# chlorophyll_analyzer_attachment.net
KiCad netlist of a schematic drawn in EAGLE
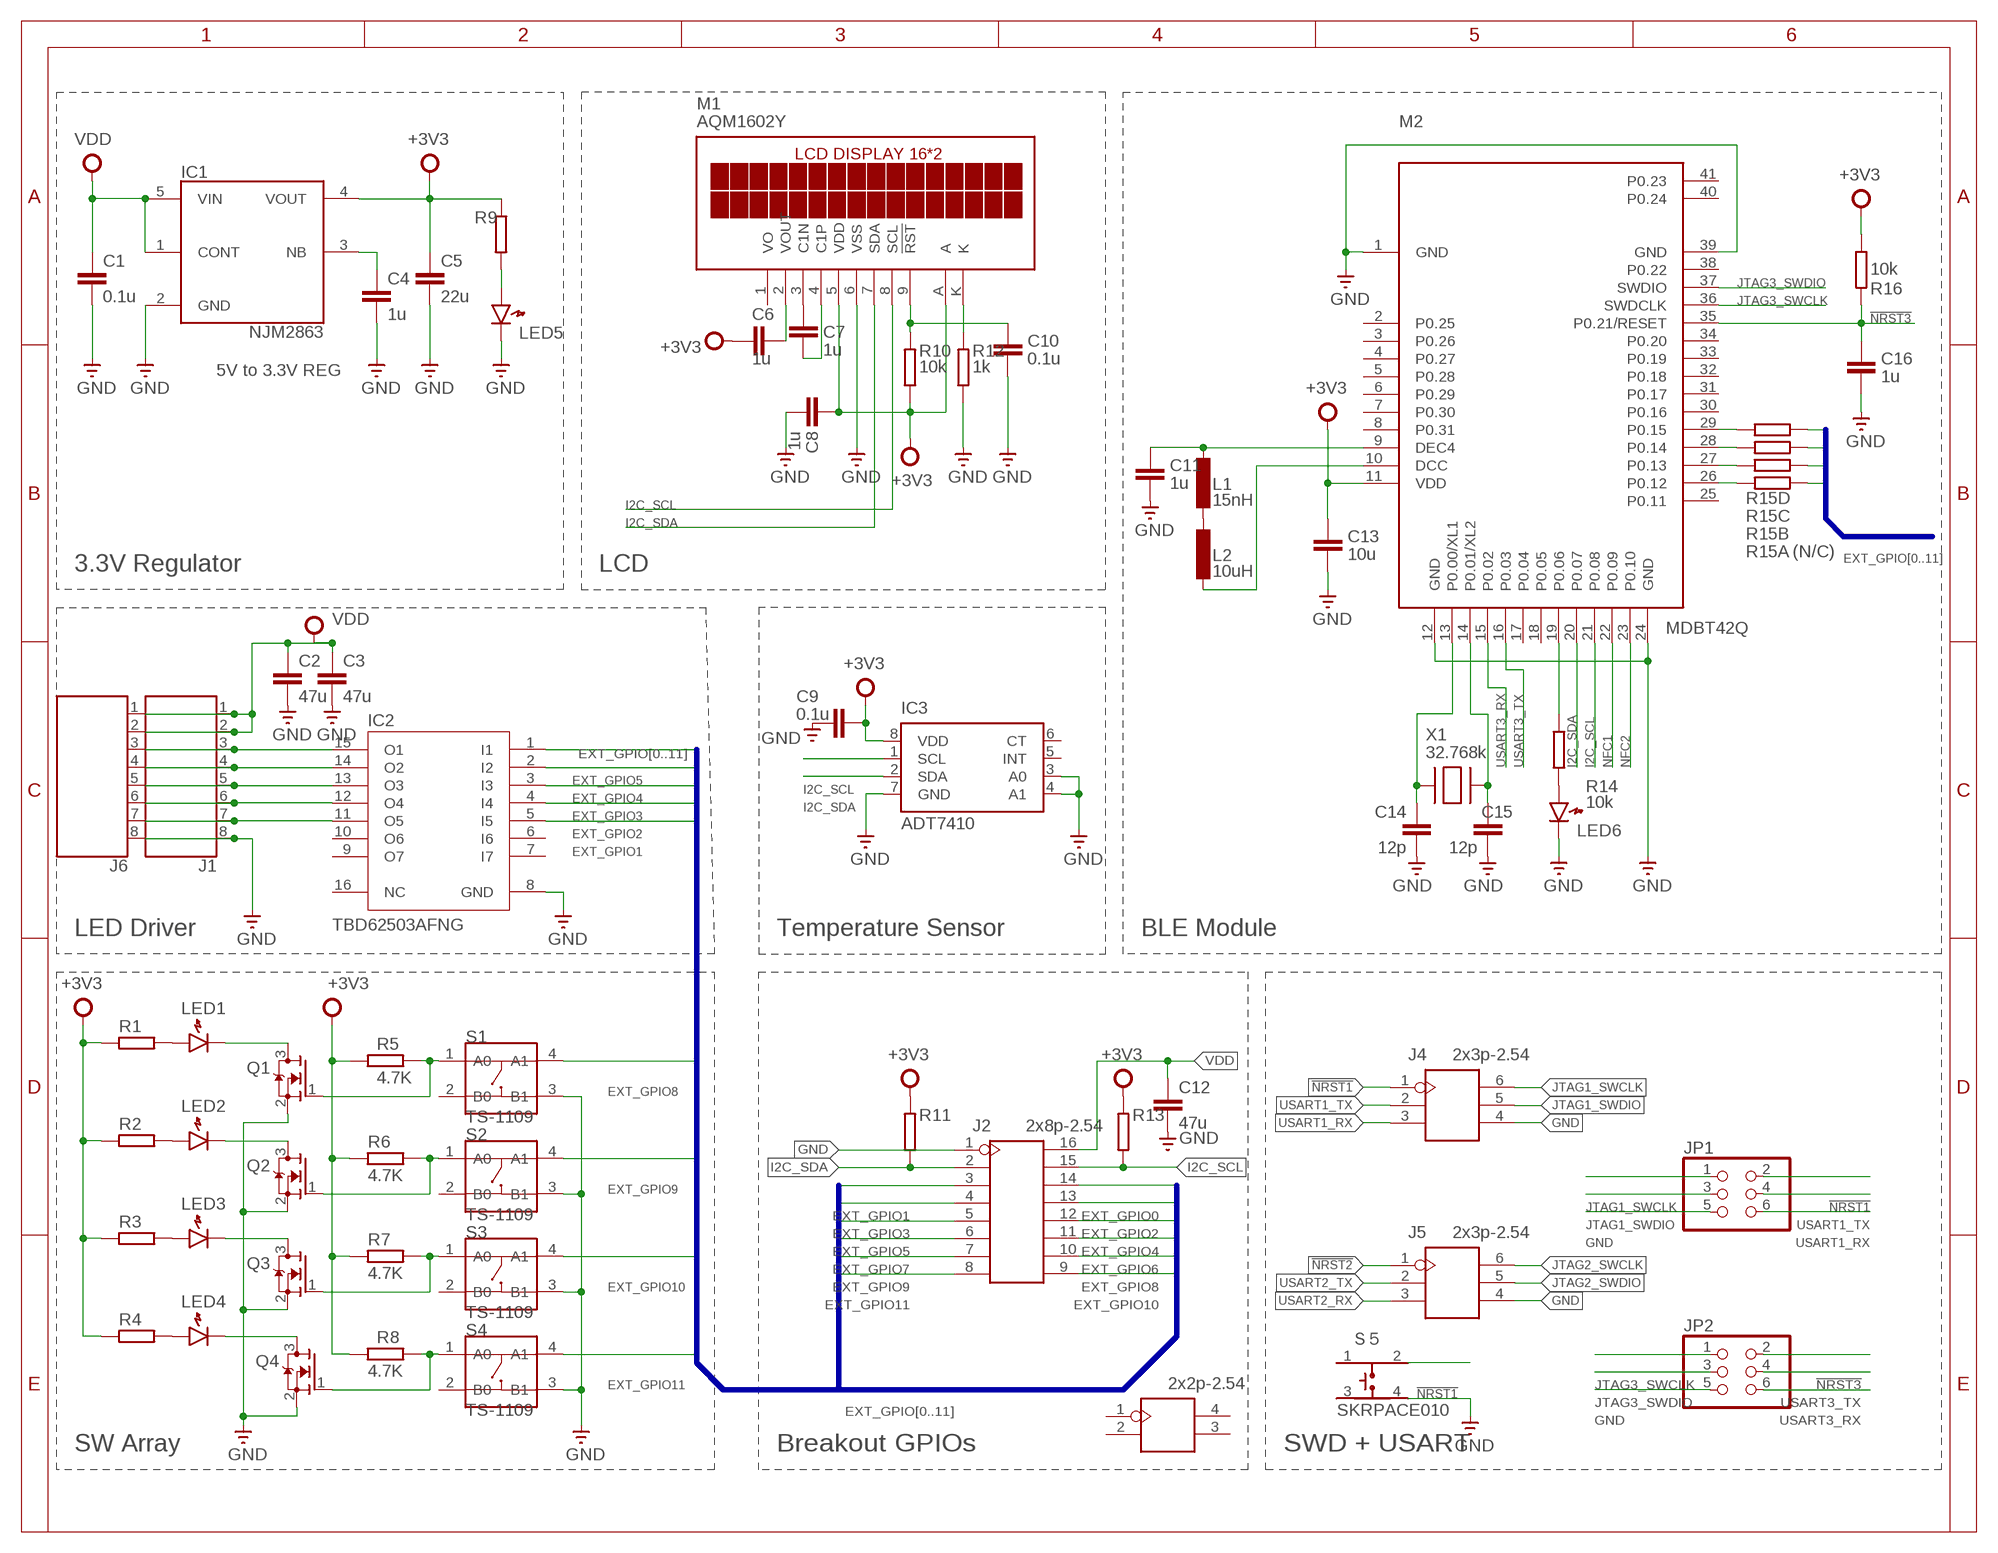
[diagram p0: schematic, sheet 1]

(export (version "E")
  (design (tool "Eeschema 10.0.6"))
  (components
    (comp (ref "C1")
      (value "0.1u")
      (footprint "eagle-import:C0603K")
      (libsource (lib "eagle-import") (part "C-EUC0603K"))
    )
    (comp (ref "C2")
      (value "47u")
      (footprint "eagle-import:C1206")
      (libsource (lib "eagle-import") (part "C-EUC1206"))
    )
    (comp (ref "C3")
      (value "47u")
      (footprint "eagle-import:C1206")
      (libsource (lib "eagle-import") (part "C-EUC1206"))
    )
    (comp (ref "C4")
      (value "1u")
      (footprint "eagle-import:C0603K")
      (libsource (lib "eagle-import") (part "C-EUC0603K"))
    )
    (comp (ref "C5")
      (value "22u")
      (footprint "eagle-import:C0603K")
      (libsource (lib "eagle-import") (part "C-EUC0603K"))
    )
    (comp (ref "C6")
      (value "1u")
      (footprint "eagle-import:C0603K")
      (libsource (lib "eagle-import") (part "C-EUC0603K"))
    )
    (comp (ref "C7")
      (value "1u")
      (footprint "eagle-import:C0603K")
      (libsource (lib "eagle-import") (part "C-EUC0603K"))
    )
    (comp (ref "C8")
      (value "1u")
      (footprint "eagle-import:C0603K")
      (libsource (lib "eagle-import") (part "C-EUC0603K"))
    )
    (comp (ref "C9")
      (value "0.1u")
      (footprint "eagle-import:C0603K")
      (libsource (lib "eagle-import") (part "C-EUC0603K"))
    )
    (comp (ref "C10")
      (value "0.1u")
      (footprint "eagle-import:C0603K")
      (libsource (lib "eagle-import") (part "C-EUC0603K"))
    )
    (comp (ref "C11")
      (value "1u")
      (footprint "eagle-import:C0603K")
      (libsource (lib "eagle-import") (part "C-EUC0603K"))
    )
    (comp (ref "C12")
      (value "47u")
      (footprint "eagle-import:C1206")
      (libsource (lib "eagle-import") (part "C-EUC1206"))
    )
    (comp (ref "C13")
      (value "10u")
      (footprint "eagle-import:C0603K")
      (libsource (lib "eagle-import") (part "C-EUC0603K"))
    )
    (comp (ref "C14")
      (value "12p")
      (footprint "eagle-import:C0603K")
      (libsource (lib "eagle-import") (part "C-EUC0603K"))
    )
    (comp (ref "C15")
      (value "12p")
      (footprint "eagle-import:C0603K")
      (libsource (lib "eagle-import") (part "C-EUC0603K"))
    )
    (comp (ref "C16")
      (value "1u")
      (footprint "eagle-import:C0603K")
      (libsource (lib "eagle-import") (part "C-EUC0603K"))
    )
    (comp (ref "IC1")
      (value "NJM2863")
      (footprint "eagle-import:SOT-23-5")
      (libsource (lib "eagle-import") (part "NJM2863"))
    )
    (comp (ref "IC2")
      (value "TBD62503AFNG")
      (footprint "eagle-import:SSOP16-P-225-0.65B")
      (libsource (lib "eagle-import") (part "TBD62503AFNG"))
    )
    (comp (ref "IC3")
      (value "ADT7410")
      (footprint "eagle-import:SOIC8")
      (fields
        (field (name "DIGI-KEY_PART_NUMBER") "ADT7410TRZ-REEL7CT-ND")
        (field (name "MF") "Analog Devices")
      )
      (libsource (lib "eagle-import") (part "ADT7410"))
    )
    (comp (ref "J1")
      (value "687108183722")
      (footprint "eagle-import:687108183722")
      (libsource (lib "eagle-import") (part "687108183722"))
    )
    (comp (ref "J2")
      (value "2x8p-2.54")
      (footprint "eagle-import:H2X8-2.54")
      (fields (field (name "MPN") "F185-1216A0BSYA1"))
      (libsource (lib "eagle-import") (part "DIP-BLACK-FEMALE-HEADER-VERT(2X8P-2.54)"))
    )
    (comp (ref "J3")
      (value "2x2p-2.54")
      (footprint "eagle-import:H2X2-2.54")
      (libsource (lib "eagle-import") (part "DIP-BLACK-FEMALE-HEADER-VERT(2X2P-2.54)"))
    )
    (comp (ref "J4")
      (value "2x3p-2.54")
      (footprint "eagle-import:H2X3-2.54")
      (fields (field (name "MPN") "F185-1203A1BSYA1"))
      (libsource (lib "eagle-import") (part "DIP-BLACK-FEMALE-HEADER-VERT(2X3P-2.54)"))
    )
    (comp (ref "J5")
      (value "2x3p-2.54")
      (footprint "eagle-import:H2X3-2.54")
      (fields (field (name "MPN") "F185-1203A1BSYA1"))
      (libsource (lib "eagle-import") (part "DIP-BLACK-FEMALE-HEADER-VERT(2X3P-2.54)"))
    )
    (comp (ref "J6")
      (value "687108183722")
      (footprint "eagle-import:687108183722")
      (libsource (lib "eagle-import") (part "687108183722"))
    )
    (comp (ref "JP1")
      (value "PINHD-2X3")
      (footprint "eagle-import:2X03")
      (libsource (lib "eagle-import") (part "PINHD-2X3"))
    )
    (comp (ref "JP2")
      (value "PINHD-2X3")
      (footprint "eagle-import:2X03")
      (libsource (lib "eagle-import") (part "PINHD-2X3"))
    )
    (comp (ref "L1")
      (value "15nH")
      (footprint "eagle-import:SMD1608")
      (libsource (lib "eagle-import") (part "INDUCOR1608"))
    )
    (comp (ref "L2")
      (value "10uH")
      (footprint "eagle-import:SMD1608")
      (libsource (lib "eagle-import") (part "INDUCOR1608"))
    )
    (comp (ref "LED1")
      (value "LED1608")
      (footprint "eagle-import:LED1608")
      (libsource (lib "eagle-import") (part "LED1608"))
    )
    (comp (ref "LED2")
      (value "LED1608")
      (footprint "eagle-import:LED1608")
      (libsource (lib "eagle-import") (part "LED1608"))
    )
    (comp (ref "LED3")
      (value "LED1608")
      (footprint "eagle-import:LED1608")
      (libsource (lib "eagle-import") (part "LED1608"))
    )
    (comp (ref "LED4")
      (value "LED1608")
      (footprint "eagle-import:LED1608")
      (libsource (lib "eagle-import") (part "LED1608"))
    )
    (comp (ref "LED5")
      (value "LED1608")
      (footprint "eagle-import:LED1608")
      (libsource (lib "eagle-import") (part "LED1608"))
    )
    (comp (ref "LED6")
      (value "LED1608")
      (footprint "eagle-import:LED1608")
      (libsource (lib "eagle-import") (part "LED1608"))
    )
    (comp (ref "M1")
      (value "AQM1602Y")
      (footprint "eagle-import:AQM1602Y")
      (libsource (lib "eagle-import") (part "AQM1602Y"))
    )
    (comp (ref "M2")
      (value "MDBT42Q")
      (footprint "eagle-import:MDBT42Q")
      (libsource (lib "eagle-import") (part "MDBT42Q"))
    )
    (comp (ref "Q1")
      (value "MOSFET-NREFLOW")
      (footprint "eagle-import:SOT23")
      (libsource (lib "eagle-import") (part "MOSFET-NREFLOW"))
    )
    (comp (ref "Q2")
      (value "MOSFET-NREFLOW")
      (footprint "eagle-import:SOT23")
      (libsource (lib "eagle-import") (part "MOSFET-NREFLOW"))
    )
    (comp (ref "Q3")
      (value "MOSFET-NREFLOW")
      (footprint "eagle-import:SOT23")
      (libsource (lib "eagle-import") (part "MOSFET-NREFLOW"))
    )
    (comp (ref "Q4")
      (value "MOSFET-NREFLOW")
      (footprint "eagle-import:SOT23")
      (libsource (lib "eagle-import") (part "MOSFET-NREFLOW"))
    )
    (comp (ref "R1")
      (value "RESISTOR1608")
      (footprint "eagle-import:SMD1608")
      (libsource (lib "eagle-import") (part "RESISTOR1608"))
    )
    (comp (ref "R2")
      (value "RESISTOR1608")
      (footprint "eagle-import:SMD1608")
      (libsource (lib "eagle-import") (part "RESISTOR1608"))
    )
    (comp (ref "R3")
      (value "RESISTOR1608")
      (footprint "eagle-import:SMD1608")
      (libsource (lib "eagle-import") (part "RESISTOR1608"))
    )
    (comp (ref "R4")
      (value "RESISTOR1608")
      (footprint "eagle-import:SMD1608")
      (libsource (lib "eagle-import") (part "RESISTOR1608"))
    )
    (comp (ref "R5")
      (value "4.7K")
      (footprint "eagle-import:SMD1608")
      (libsource (lib "eagle-import") (part "RESISTOR1608"))
    )
    (comp (ref "R6")
      (value "4.7K")
      (footprint "eagle-import:SMD1608")
      (libsource (lib "eagle-import") (part "RESISTOR1608"))
    )
    (comp (ref "R7")
      (value "4.7K")
      (footprint "eagle-import:SMD1608")
      (libsource (lib "eagle-import") (part "RESISTOR1608"))
    )
    (comp (ref "R8")
      (value "4.7K")
      (footprint "eagle-import:SMD1608")
      (libsource (lib "eagle-import") (part "RESISTOR1608"))
    )
    (comp (ref "R9")
      (value "RESISTOR1608")
      (footprint "eagle-import:SMD1608")
      (libsource (lib "eagle-import") (part "RESISTOR1608"))
    )
    (comp (ref "R10")
      (value "10k")
      (footprint "eagle-import:SMD1608")
      (libsource (lib "eagle-import") (part "RESISTOR1608"))
    )
    (comp (ref "R11")
      (value "RESISTOR1608")
      (footprint "eagle-import:SMD1608")
      (libsource (lib "eagle-import") (part "RESISTOR1608"))
    )
    (comp (ref "R12")
      (value "1k")
      (footprint "eagle-import:SMD1608")
      (libsource (lib "eagle-import") (part "RESISTOR1608"))
    )
    (comp (ref "R13")
      (value "RESISTOR1608")
      (footprint "eagle-import:SMD1608")
      (libsource (lib "eagle-import") (part "RESISTOR1608"))
    )
    (comp (ref "R14")
      (value "10k")
      (footprint "eagle-import:SMD1608")
      (libsource (lib "eagle-import") (part "RESISTOR1608"))
    )
    (comp (ref "R15")
      (value "(N/C)")
      (footprint "eagle-import:RESCAXS80P320X160X60-8N")
      (libsource (lib "eagle-import") (part "RESISTOR_ARRY1206"))
    )
    (comp (ref "R16")
      (value "10k")
      (footprint "eagle-import:SMD1608")
      (libsource (lib "eagle-import") (part "RESISTOR1608"))
    )
    (comp (ref "S1")
      (value "TS-1109")
      (footprint "eagle-import:SW4-6.0X6.0X5.0MM")
      (fields (field (name "SPICEPREFIX") "K"))
      (libsource (lib "eagle-import") (part "DIP-BUTTON-4P"))
    )
    (comp (ref "S2")
      (value "TS-1109")
      (footprint "eagle-import:SW4-6.0X6.0X5.0MM")
      (fields (field (name "SPICEPREFIX") "K"))
      (libsource (lib "eagle-import") (part "DIP-BUTTON-4P"))
    )
    (comp (ref "S3")
      (value "TS-1109")
      (footprint "eagle-import:SW4-6.0X6.0X5.0MM")
      (fields (field (name "SPICEPREFIX") "K"))
      (libsource (lib "eagle-import") (part "DIP-BUTTON-4P"))
    )
    (comp (ref "S4")
      (value "TS-1109")
      (footprint "eagle-import:SW4-6.0X6.0X5.0MM")
      (fields (field (name "SPICEPREFIX") "K"))
      (libsource (lib "eagle-import") (part "DIP-BUTTON-4P"))
    )
    (comp (ref "S５")
      (value "SKRPACE010")
      (footprint "eagle-import:SW_SKRPACE010")
      (fields (field (name "MF") "ALPS") (field (name "SPICEPREFIX") "S"))
      (libsource (lib "eagle-import") (part "SKRPACE010"))
    )
    (comp (ref "X1")
      (value "32.768k")
      (footprint "eagle-import:XTAL3215")
      (fields (field (name "SPICEPREFIX") "X"))
      (libsource (lib "eagle-import") (part "XTAL-3.2X1.5"))
    )
  )
  (nets
    (net (code "1") (name "+3V3") (class "Default")
      (node (ref "C13") (pin "1") (pinfunction "1_1") (pintype "passive"))
      (node (ref "C5") (pin "1") (pinfunction "1_1") (pintype "passive"))
      (node (ref "C6") (pin "1") (pinfunction "1_1") (pintype "passive"))
      (node (ref "C8") (pin "2") (pinfunction "2_2") (pintype "passive"))
      (node (ref "C9") (pin "1") (pinfunction "1_1") (pintype "passive"))
      (node (ref "IC1") (pin "4") (pinfunction "VOUT_4") (pintype "bidirectional"))
      (node (ref "IC3") (pin "8") (pinfunction "VDD_8") (pintype "power_in"))
      (node (ref "M1") (pin "5") (pinfunction "VDD_5") (pintype "power_in"))
      (node (ref "M1") (pin "A") (pinfunction "A_A") (pintype "bidirectional"))
      (node (ref "M2") (pin "11") (pinfunction "VDD_11") (pintype "bidirectional"))
      (node (ref "R1") (pin "1") (pinfunction "1_1") (pintype "passive"))
      (node (ref "R10") (pin "2") (pinfunction "2_2") (pintype "passive"))
      (node (ref "R11") (pin "1") (pinfunction "1_1") (pintype "passive"))
      (node (ref "R13") (pin "1") (pinfunction "1_1") (pintype "passive"))
      (node (ref "R16") (pin "2") (pinfunction "2_2") (pintype "passive"))
      (node (ref "R2") (pin "1") (pinfunction "1_1") (pintype "passive"))
      (node (ref "R3") (pin "1") (pinfunction "1_1") (pintype "passive"))
      (node (ref "R4") (pin "1") (pinfunction "1_1") (pintype "passive"))
      (node (ref "R5") (pin "1") (pinfunction "1_1") (pintype "passive"))
      (node (ref "R6") (pin "1") (pinfunction "1_1") (pintype "passive"))
      (node (ref "R7") (pin "1") (pinfunction "1_1") (pintype "passive"))
      (node (ref "R8") (pin "1") (pinfunction "1_1") (pintype "passive"))
      (node (ref "R9") (pin "1") (pinfunction "1_1") (pintype "passive"))
    )
    (net (code "2") (name "/EXT_GPIO0") (class "Default")
      (node (ref "J2") (pin "14") (pinfunction "14_14") (pintype "bidirectional"))
    )
    (net (code "3") (name "/EXT_GPIO1") (class "Default")
      (node (ref "IC2") (pin "5") (pinfunction "I5_5") (pintype "input"))
      (node (ref "J2") (pin "3") (pinfunction "3_3") (pintype "bidirectional"))
    )
    (net (code "4") (name "/EXT_GPIO2") (class "Default")
      (node (ref "IC2") (pin "4") (pinfunction "I4_4") (pintype "input"))
      (node (ref "J2") (pin "13") (pinfunction "13_13") (pintype "bidirectional"))
    )
    (net (code "5") (name "/EXT_GPIO3") (class "Default")
      (node (ref "IC2") (pin "3") (pinfunction "I3_3") (pintype "input"))
      (node (ref "J2") (pin "4") (pinfunction "4_4") (pintype "bidirectional"))
    )
    (net (code "6") (name "/EXT_GPIO4") (class "Default")
      (node (ref "IC2") (pin "2") (pinfunction "I2_2") (pintype "input"))
      (node (ref "J2") (pin "12") (pinfunction "12_12") (pintype "bidirectional"))
    )
    (net (code "7") (name "/EXT_GPIO5") (class "Default")
      (node (ref "IC2") (pin "1") (pinfunction "I1_1") (pintype "input"))
      (node (ref "J2") (pin "5") (pinfunction "5_5") (pintype "bidirectional"))
    )
    (net (code "8") (name "/EXT_GPIO6") (class "Default")
      (node (ref "J2") (pin "11") (pinfunction "11_11") (pintype "bidirectional"))
    )
    (net (code "9") (name "/EXT_GPIO7") (class "Default")
      (node (ref "J2") (pin "6") (pinfunction "6_6") (pintype "bidirectional"))
    )
    (net (code "10") (name "/EXT_GPIO8") (class "Default")
      (node (ref "J2") (pin "10") (pinfunction "10_10") (pintype "bidirectional"))
      (node (ref "R15") (pin "8") (pinfunction "2_8") (pintype "passive"))
      (node (ref "S1") (pin "4") (pinfunction "A1_4") (pintype "bidirectional"))
    )
    (net (code "11") (name "/EXT_GPIO9") (class "Default")
      (node (ref "J2") (pin "7") (pinfunction "7_7") (pintype "bidirectional"))
      (node (ref "R15") (pin "7") (pinfunction "2_7") (pintype "passive"))
      (node (ref "S2") (pin "4") (pinfunction "A1_4") (pintype "bidirectional"))
    )
    (net (code "12") (name "/EXT_GPIO10") (class "Default")
      (node (ref "J2") (pin "9") (pinfunction "9_9") (pintype "bidirectional"))
      (node (ref "R15") (pin "6") (pinfunction "2_6") (pintype "passive"))
      (node (ref "S3") (pin "4") (pinfunction "A1_4") (pintype "bidirectional"))
    )
    (net (code "13") (name "/EXT_GPIO11") (class "Default")
      (node (ref "J2") (pin "8") (pinfunction "8_8") (pintype "bidirectional"))
      (node (ref "R15") (pin "5") (pinfunction "2_5") (pintype "passive"))
      (node (ref "S4") (pin "4") (pinfunction "A1_4") (pintype "bidirectional"))
    )
    (net (code "15") (name "/JTAG3_SWCLK") (class "Default")
      (node (ref "JP2") (pin "1") (pinfunction "1_1") (pintype "passive"))
      (node (ref "M2") (pin "36") (pinfunction "SWDCLK_36") (pintype "bidirectional"))
    )
    (net (code "16") (name "/JTAG3_SWDIO") (class "Default")
      (node (ref "JP2") (pin "3") (pinfunction "3_3") (pintype "passive"))
      (node (ref "M2") (pin "37") (pinfunction "SWDIO_37") (pintype "bidirectional"))
    )
    (net (code "17") (name "/NFC1") (class "Default")
      (node (ref "M2") (pin "22") (pinfunction "P0.09_22") (pintype "bidirectional"))
    )
    (net (code "18") (name "/NFC2") (class "Default")
      (node (ref "M2") (pin "23") (pinfunction "P0.10_23") (pintype "bidirectional"))
    )
    (net (code "19") (name "/USART3_RX") (class "Default")
      (node (ref "JP2") (pin "6") (pinfunction "6_6") (pintype "passive"))
      (node (ref "M2") (pin "15") (pinfunction "P0.02_15") (pintype "bidirectional"))
    )
    (net (code "20") (name "/USART3_TX") (class "Default")
      (node (ref "JP2") (pin "4") (pinfunction "4_4") (pintype "passive"))
      (node (ref "M2") (pin "16") (pinfunction "P0.03_16") (pintype "bidirectional"))
    )
    (net (code "21") (name "/~{NRST1}") (class "Default")
      (node (ref "J4") (pin "1") (pinfunction "1_1") (pintype "bidirectional"))
      (node (ref "JP1") (pin "2") (pinfunction "2_2") (pintype "passive"))
      (node (ref "S５") (pin "2") (pinfunction "2_2") (pintype "bidirectional"))
    )
    (net (code "22") (name "/~{NRST2}") (class "Default")
      (node (ref "J5") (pin "1") (pinfunction "1_1") (pintype "bidirectional"))
    )
    (net (code "23") (name "/~{NRST3}") (class "Default")
      (node (ref "C16") (pin "1") (pinfunction "1_1") (pintype "passive"))
      (node (ref "JP2") (pin "2") (pinfunction "2_2") (pintype "passive"))
      (node (ref "M2") (pin "35") (pinfunction "P0.21/RESET_35") (pintype "bidirectional"))
      (node (ref "R16") (pin "1") (pinfunction "1_1") (pintype "passive"))
    )
    (net (code "24") (name "GND") (class "Default")
      (node (ref "C1") (pin "2") (pinfunction "2_2") (pintype "passive"))
      (node (ref "C10") (pin "2") (pinfunction "2_2") (pintype "passive"))
      (node (ref "C11") (pin "2") (pinfunction "2_2") (pintype "passive"))
      (node (ref "C12") (pin "2") (pinfunction "2_2") (pintype "passive"))
      (node (ref "C13") (pin "2") (pinfunction "2_2") (pintype "passive"))
      (node (ref "C14") (pin "2") (pinfunction "2_2") (pintype "passive"))
      (node (ref "C15") (pin "2") (pinfunction "2_2") (pintype "passive"))
      (node (ref "C16") (pin "2") (pinfunction "2_2") (pintype "passive"))
      (node (ref "C2") (pin "2") (pinfunction "2_2") (pintype "passive"))
      (node (ref "C3") (pin "2") (pinfunction "2_2") (pintype "passive"))
      (node (ref "C4") (pin "2") (pinfunction "2_2") (pintype "passive"))
      (node (ref "C5") (pin "2") (pinfunction "2_2") (pintype "passive"))
      (node (ref "C8") (pin "1") (pinfunction "1_1") (pintype "passive"))
      (node (ref "C9") (pin "2") (pinfunction "2_2") (pintype "passive"))
      (node (ref "IC1") (pin "2") (pinfunction "GND_2") (pintype "bidirectional"))
      (node (ref "IC2") (pin "8") (pinfunction "GND_8") (pintype "power_in"))
      (node (ref "IC3") (pin "3") (pinfunction "A0_3") (pintype "bidirectional"))
      (node (ref "IC3") (pin "4") (pinfunction "A1_4") (pintype "bidirectional"))
      (node (ref "IC3") (pin "7") (pinfunction "GND_7") (pintype "power_in"))
      (node (ref "J1") (pin "8") (pinfunction "1_8") (pintype "passive"))
      (node (ref "J2") (pin "1") (pinfunction "1_1") (pintype "bidirectional"))
      (node (ref "J4") (pin "4") (pinfunction "4_4") (pintype "bidirectional"))
      (node (ref "J5") (pin "4") (pinfunction "4_4") (pintype "bidirectional"))
      (node (ref "J6") (pin "8") (pinfunction "1_8") (pintype "passive"))
      (node (ref "JP1") (pin "5") (pinfunction "5_5") (pintype "passive"))
      (node (ref "JP2") (pin "5") (pinfunction "5_5") (pintype "passive"))
      (node (ref "LED5") (pin "K") (pinfunction "K_K") (pintype "passive"))
      (node (ref "LED6") (pin "K") (pinfunction "K_K") (pintype "passive"))
      (node (ref "M1") (pin "6") (pinfunction "VSS_6") (pintype "power_in"))
      (node (ref "M2") (pin "1") (pinfunction "GND_1") (pintype "bidirectional"))
      (node (ref "M2") (pin "12") (pinfunction "GND_12") (pintype "bidirectional"))
      (node (ref "M2") (pin "24") (pinfunction "GND_24") (pintype "bidirectional"))
      (node (ref "M2") (pin "39") (pinfunction "GND_39") (pintype "bidirectional"))
      (node (ref "Q1") (pin "2") (pinfunction "S_2") (pintype "bidirectional"))
      (node (ref "Q2") (pin "2") (pinfunction "S_2") (pintype "bidirectional"))
      (node (ref "Q3") (pin "2") (pinfunction "S_2") (pintype "bidirectional"))
      (node (ref "Q4") (pin "2") (pinfunction "S_2") (pintype "bidirectional"))
      (node (ref "R12") (pin "2") (pinfunction "2_2") (pintype "passive"))
      (node (ref "S1") (pin "3") (pinfunction "B1_3") (pintype "bidirectional"))
      (node (ref "S2") (pin "3") (pinfunction "B1_3") (pintype "bidirectional"))
      (node (ref "S3") (pin "3") (pinfunction "B1_3") (pintype "bidirectional"))
      (node (ref "S4") (pin "3") (pinfunction "B1_3") (pintype "bidirectional"))
      (node (ref "S５") (pin "4") (pinfunction "4_4") (pintype "bidirectional"))
    )
    (net (code "25") (name "I2C_SCL") (class "Default")
      (node (ref "IC3") (pin "1") (pinfunction "SCL_1") (pintype "bidirectional"))
      (node (ref "J2") (pin "15") (pinfunction "15_15") (pintype "bidirectional"))
      (node (ref "M1") (pin "8") (pinfunction "SCL_8") (pintype "input"))
      (node (ref "M2") (pin "21") (pinfunction "P0.08_21") (pintype "bidirectional"))
      (node (ref "R13") (pin "2") (pinfunction "2_2") (pintype "passive"))
    )
    (net (code "26") (name "I2C_SDA") (class "Default")
      (node (ref "IC3") (pin "2") (pinfunction "SDA_2") (pintype "bidirectional"))
      (node (ref "J2") (pin "2") (pinfunction "2_2") (pintype "bidirectional"))
      (node (ref "M1") (pin "7") (pinfunction "SDA_7") (pintype "bidirectional"))
      (node (ref "M2") (pin "20") (pinfunction "P0.07_20") (pintype "bidirectional"))
      (node (ref "R11") (pin "2") (pinfunction "2_2") (pintype "passive"))
    )
    (net (code "27") (name "JTAG1_SWCLK") (class "Default")
      (node (ref "J4") (pin "6") (pinfunction "6_6") (pintype "bidirectional"))
      (node (ref "JP1") (pin "1") (pinfunction "1_1") (pintype "passive"))
    )
    (net (code "28") (name "JTAG1_SWDIO") (class "Default")
      (node (ref "J4") (pin "5") (pinfunction "5_5") (pintype "bidirectional"))
      (node (ref "JP1") (pin "3") (pinfunction "3_3") (pintype "passive"))
    )
    (net (code "29") (name "JTAG2_SWCLK") (class "Default")
      (node (ref "J5") (pin "6") (pinfunction "6_6") (pintype "bidirectional"))
    )
    (net (code "30") (name "JTAG2_SWDIO") (class "Default")
      (node (ref "J5") (pin "5") (pinfunction "5_5") (pintype "bidirectional"))
    )
    (net (code "31") (name "Net-(IC1-NB)") (class "Default")
      (node (ref "C4") (pin "1") (pinfunction "1_1") (pintype "passive"))
      (node (ref "IC1") (pin "3") (pinfunction "NB_3") (pintype "bidirectional"))
    )
    (net (code "32") (name "Net-(IC2-O1)") (class "Default")
      (node (ref "IC2") (pin "15") (pinfunction "O1_15") (pintype "output"))
      (node (ref "J1") (pin "3") (pinfunction "6_3") (pintype "passive"))
      (node (ref "J6") (pin "3") (pinfunction "6_3") (pintype "passive"))
    )
    (net (code "33") (name "Net-(IC2-O2)") (class "Default")
      (node (ref "IC2") (pin "14") (pinfunction "O2_14") (pintype "output"))
      (node (ref "J1") (pin "4") (pinfunction "5_4") (pintype "passive"))
      (node (ref "J6") (pin "4") (pinfunction "5_4") (pintype "passive"))
    )
    (net (code "34") (name "Net-(IC2-O3)") (class "Default")
      (node (ref "IC2") (pin "13") (pinfunction "O3_13") (pintype "output"))
      (node (ref "J1") (pin "5") (pinfunction "4_5") (pintype "passive"))
      (node (ref "J6") (pin "5") (pinfunction "4_5") (pintype "passive"))
    )
    (net (code "35") (name "Net-(IC2-O4)") (class "Default")
      (node (ref "IC2") (pin "12") (pinfunction "O4_12") (pintype "output"))
      (node (ref "J1") (pin "6") (pinfunction "3_6") (pintype "passive"))
      (node (ref "J6") (pin "6") (pinfunction "3_6") (pintype "passive"))
    )
    (net (code "36") (name "Net-(IC2-O5)") (class "Default")
      (node (ref "IC2") (pin "11") (pinfunction "O5_11") (pintype "output"))
      (node (ref "J1") (pin "7") (pinfunction "2_7") (pintype "passive"))
      (node (ref "J6") (pin "7") (pinfunction "2_7") (pintype "passive"))
    )
    (net (code "37") (name "Net-(L1-Pad2)") (class "Default")
      (node (ref "L1") (pin "2") (pinfunction "2_2") (pintype "passive"))
      (node (ref "L2") (pin "1") (pinfunction "1_1") (pintype "passive"))
    )
    (net (code "38") (name "Net-(LED1-PadA)") (class "Default")
      (node (ref "LED1") (pin "A") (pinfunction "A_A") (pintype "passive"))
      (node (ref "R1") (pin "2") (pinfunction "2_2") (pintype "passive"))
    )
    (net (code "39") (name "Net-(LED2-PadA)") (class "Default")
      (node (ref "LED2") (pin "A") (pinfunction "A_A") (pintype "passive"))
      (node (ref "R2") (pin "2") (pinfunction "2_2") (pintype "passive"))
    )
    (net (code "40") (name "Net-(LED3-PadA)") (class "Default")
      (node (ref "LED3") (pin "A") (pinfunction "A_A") (pintype "passive"))
      (node (ref "R3") (pin "2") (pinfunction "2_2") (pintype "passive"))
    )
    (net (code "41") (name "Net-(LED4-PadA)") (class "Default")
      (node (ref "LED4") (pin "A") (pinfunction "A_A") (pintype "passive"))
      (node (ref "R4") (pin "2") (pinfunction "2_2") (pintype "passive"))
    )
    (net (code "42") (name "Net-(LED5-PadA)") (class "Default")
      (node (ref "LED5") (pin "A") (pinfunction "A_A") (pintype "passive"))
      (node (ref "R9") (pin "2") (pinfunction "2_2") (pintype "passive"))
    )
    (net (code "43") (name "Net-(LED6-PadA)") (class "Default")
      (node (ref "LED6") (pin "A") (pinfunction "A_A") (pintype "passive"))
      (node (ref "R14") (pin "1") (pinfunction "1_1") (pintype "passive"))
    )
    (net (code "44") (name "Net-(M1-C1N)") (class "Default")
      (node (ref "C7") (pin "2") (pinfunction "2_2") (pintype "passive"))
      (node (ref "M1") (pin "3") (pinfunction "C1N_3") (pintype "input"))
    )
    (net (code "45") (name "Net-(M1-C1P)") (class "Default")
      (node (ref "C7") (pin "1") (pinfunction "1_1") (pintype "passive"))
      (node (ref "M1") (pin "4") (pinfunction "C1P_4") (pintype "input"))
    )
    (net (code "46") (name "Net-(M1-PadK)") (class "Default")
      (node (ref "M1") (pin "K") (pinfunction "K_K") (pintype "bidirectional"))
      (node (ref "R12") (pin "1") (pinfunction "1_1") (pintype "passive"))
    )
    (net (code "47") (name "Net-(M1-VOUT)") (class "Default")
      (node (ref "C6") (pin "2") (pinfunction "2_2") (pintype "passive"))
      (node (ref "M1") (pin "2") (pinfunction "VOUT_2") (pintype "output"))
    )
    (net (code "48") (name "Net-(M1-~{RST})") (class "Default")
      (node (ref "C10") (pin "1") (pinfunction "1_1") (pintype "passive"))
      (node (ref "M1") (pin "9") (pinfunction "~{RST}_9") (pintype "input"))
      (node (ref "R10") (pin "1") (pinfunction "1_1") (pintype "passive"))
    )
    (net (code "49") (name "Net-(M2-DCC)") (class "Default")
      (node (ref "L2") (pin "2") (pinfunction "2_2") (pintype "passive"))
      (node (ref "M2") (pin "10") (pinfunction "DCC_10") (pintype "bidirectional"))
    )
    (net (code "50") (name "Net-(M2-DEC4)") (class "Default")
      (node (ref "C11") (pin "1") (pinfunction "1_1") (pintype "passive"))
      (node (ref "L1") (pin "1") (pinfunction "1_1") (pintype "passive"))
      (node (ref "M2") (pin "9") (pinfunction "DEC4_9") (pintype "bidirectional"))
    )
    (net (code "51") (name "Net-(M2-P0.00{slash}XL1)") (class "Default")
      (node (ref "C14") (pin "1") (pinfunction "1_1") (pintype "passive"))
      (node (ref "M2") (pin "13") (pinfunction "P0.00/XL1_13") (pintype "bidirectional"))
      (node (ref "X1") (pin "P$1") (pinfunction "P$1_P$1") (pintype "bidirectional"))
    )
    (net (code "52") (name "Net-(M2-P0.01{slash}XL2)") (class "Default")
      (node (ref "C15") (pin "1") (pinfunction "1_1") (pintype "passive"))
      (node (ref "M2") (pin "14") (pinfunction "P0.01/XL2_14") (pintype "bidirectional"))
      (node (ref "X1") (pin "P$2") (pinfunction "P$2_P$2") (pintype "bidirectional"))
    )
    (net (code "53") (name "Net-(M2-P0.06)") (class "Default")
      (node (ref "M2") (pin "19") (pinfunction "P0.06_19") (pintype "bidirectional"))
      (node (ref "R14") (pin "2") (pinfunction "2_2") (pintype "passive"))
    )
    (net (code "54") (name "Net-(M2-P0.12)") (class "Default")
      (node (ref "M2") (pin "26") (pinfunction "P0.12_26") (pintype "bidirectional"))
      (node (ref "R15") (pin "1") (pinfunction "1_1") (pintype "passive"))
    )
    (net (code "55") (name "Net-(M2-P0.13)") (class "Default")
      (node (ref "M2") (pin "27") (pinfunction "P0.13_27") (pintype "bidirectional"))
      (node (ref "R15") (pin "2") (pinfunction "1_2") (pintype "passive"))
    )
    (net (code "56") (name "Net-(M2-P0.14)") (class "Default")
      (node (ref "M2") (pin "28") (pinfunction "P0.14_28") (pintype "bidirectional"))
      (node (ref "R15") (pin "3") (pinfunction "1_3") (pintype "passive"))
    )
    (net (code "57") (name "Net-(M2-P0.15)") (class "Default")
      (node (ref "M2") (pin "29") (pinfunction "P0.15_29") (pintype "bidirectional"))
      (node (ref "R15") (pin "4") (pinfunction "1_4") (pintype "passive"))
    )
    (net (code "58") (name "Net-(Q1-D)") (class "Default")
      (node (ref "LED1") (pin "K") (pinfunction "K_K") (pintype "passive"))
      (node (ref "Q1") (pin "3") (pinfunction "D_3") (pintype "bidirectional"))
    )
    (net (code "59") (name "Net-(Q1-G)") (class "Default")
      (node (ref "Q1") (pin "1") (pinfunction "G_1") (pintype "bidirectional"))
      (node (ref "R5") (pin "2") (pinfunction "2_2") (pintype "passive"))
      (node (ref "S1") (pin "1") (pinfunction "A0_1") (pintype "bidirectional"))
    )
    (net (code "60") (name "Net-(Q2-D)") (class "Default")
      (node (ref "LED2") (pin "K") (pinfunction "K_K") (pintype "passive"))
      (node (ref "Q2") (pin "3") (pinfunction "D_3") (pintype "bidirectional"))
    )
    (net (code "61") (name "Net-(Q2-G)") (class "Default")
      (node (ref "Q2") (pin "1") (pinfunction "G_1") (pintype "bidirectional"))
      (node (ref "R6") (pin "2") (pinfunction "2_2") (pintype "passive"))
      (node (ref "S2") (pin "1") (pinfunction "A0_1") (pintype "bidirectional"))
    )
    (net (code "62") (name "Net-(Q3-D)") (class "Default")
      (node (ref "LED3") (pin "K") (pinfunction "K_K") (pintype "passive"))
      (node (ref "Q3") (pin "3") (pinfunction "D_3") (pintype "bidirectional"))
    )
    (net (code "63") (name "Net-(Q3-G)") (class "Default")
      (node (ref "Q3") (pin "1") (pinfunction "G_1") (pintype "bidirectional"))
      (node (ref "R7") (pin "2") (pinfunction "2_2") (pintype "passive"))
      (node (ref "S3") (pin "1") (pinfunction "A0_1") (pintype "bidirectional"))
    )
    (net (code "64") (name "Net-(Q4-D)") (class "Default")
      (node (ref "LED4") (pin "K") (pinfunction "K_K") (pintype "passive"))
      (node (ref "Q4") (pin "3") (pinfunction "D_3") (pintype "bidirectional"))
    )
    (net (code "65") (name "Net-(Q4-G)") (class "Default")
      (node (ref "Q4") (pin "1") (pinfunction "G_1") (pintype "bidirectional"))
      (node (ref "R8") (pin "2") (pinfunction "2_2") (pintype "passive"))
      (node (ref "S4") (pin "1") (pinfunction "A0_1") (pintype "bidirectional"))
    )
    (net (code "66") (name "USART1_RX") (class "Default")
      (node (ref "J4") (pin "3") (pinfunction "3_3") (pintype "bidirectional"))
      (node (ref "JP1") (pin "6") (pinfunction "6_6") (pintype "passive"))
    )
    (net (code "67") (name "USART1_TX") (class "Default")
      (node (ref "J4") (pin "2") (pinfunction "2_2") (pintype "bidirectional"))
      (node (ref "JP1") (pin "4") (pinfunction "4_4") (pintype "passive"))
    )
    (net (code "68") (name "USART2_RX") (class "Default")
      (node (ref "J5") (pin "3") (pinfunction "3_3") (pintype "bidirectional"))
    )
    (net (code "69") (name "USART2_TX") (class "Default")
      (node (ref "J5") (pin "2") (pinfunction "2_2") (pintype "bidirectional"))
    )
    (net (code "70") (name "VDD") (class "Default")
      (node (ref "C1") (pin "1") (pinfunction "1_1") (pintype "passive"))
      (node (ref "C12") (pin "1") (pinfunction "1_1") (pintype "passive"))
      (node (ref "C2") (pin "1") (pinfunction "1_1") (pintype "passive"))
      (node (ref "C3") (pin "1") (pinfunction "1_1") (pintype "passive"))
      (node (ref "IC1") (pin "1") (pinfunction "CONT_1") (pintype "bidirectional"))
      (node (ref "IC1") (pin "5") (pinfunction "VIN_5") (pintype "bidirectional"))
      (node (ref "J1") (pin "1") (pinfunction "8_1") (pintype "passive"))
      (node (ref "J1") (pin "2") (pinfunction "7_2") (pintype "passive"))
      (node (ref "J2") (pin "16") (pinfunction "16_16") (pintype "bidirectional"))
      (node (ref "J6") (pin "1") (pinfunction "8_1") (pintype "passive"))
      (node (ref "J6") (pin "2") (pinfunction "7_2") (pintype "passive"))
    )
    (net (code "71") (name "unconnected-(IC2-I6-Pad6)") (class "Default")
      (node (ref "IC2") (pin "6") (pinfunction "I6_6") (pintype "input"))
    )
    (net (code "72") (name "unconnected-(IC2-I7-Pad7)") (class "Default")
      (node (ref "IC2") (pin "7") (pinfunction "I7_7") (pintype "input"))
    )
    (net (code "73") (name "unconnected-(IC2-NC-Pad16)") (class "Default")
      (node (ref "IC2") (pin "16") (pinfunction "NC_16") (pintype "no_connect"))
    )
    (net (code "74") (name "unconnected-(IC2-O6-Pad10)") (class "Default")
      (node (ref "IC2") (pin "10") (pinfunction "O6_10") (pintype "output"))
    )
    (net (code "75") (name "unconnected-(IC2-O7-Pad9)") (class "Default")
      (node (ref "IC2") (pin "9") (pinfunction "O7_9") (pintype "output"))
    )
    (net (code "76") (name "unconnected-(IC3-CT-Pad6)") (class "Default")
      (node (ref "IC3") (pin "6") (pinfunction "CT_6") (pintype "bidirectional"))
    )
    (net (code "77") (name "unconnected-(IC3-INT-Pad5)") (class "Default")
      (node (ref "IC3") (pin "5") (pinfunction "INT_5") (pintype "bidirectional"))
    )
    (net (code "78") (name "unconnected-(J3-Pad1)") (class "Default")
      (node (ref "J3") (pin "1") (pinfunction "1_1") (pintype "bidirectional"))
    )
    (net (code "79") (name "unconnected-(J3-Pad2)") (class "Default")
      (node (ref "J3") (pin "2") (pinfunction "2_2") (pintype "bidirectional"))
    )
    (net (code "80") (name "unconnected-(J3-Pad3)") (class "Default")
      (node (ref "J3") (pin "3") (pinfunction "3_3") (pintype "bidirectional"))
    )
    (net (code "81") (name "unconnected-(J3-Pad4)") (class "Default")
      (node (ref "J3") (pin "4") (pinfunction "4_4") (pintype "bidirectional"))
    )
    (net (code "82") (name "unconnected-(M1-VO-Pad1)") (class "Default")
      (node (ref "M1") (pin "1") (pinfunction "VO_1") (pintype "input"))
    )
    (net (code "83") (name "unconnected-(M2-P0.04-Pad17)") (class "Default")
      (node (ref "M2") (pin "17") (pinfunction "P0.04_17") (pintype "bidirectional"))
    )
    (net (code "84") (name "unconnected-(M2-P0.05-Pad18)") (class "Default")
      (node (ref "M2") (pin "18") (pinfunction "P0.05_18") (pintype "bidirectional"))
    )
    (net (code "85") (name "unconnected-(M2-P0.11-Pad25)") (class "Default")
      (node (ref "M2") (pin "25") (pinfunction "P0.11_25") (pintype "bidirectional"))
    )
    (net (code "86") (name "unconnected-(M2-P0.16-Pad30)") (class "Default")
      (node (ref "M2") (pin "30") (pinfunction "P0.16_30") (pintype "bidirectional"))
    )
    (net (code "87") (name "unconnected-(M2-P0.17-Pad31)") (class "Default")
      (node (ref "M2") (pin "31") (pinfunction "P0.17_31") (pintype "bidirectional"))
    )
    (net (code "88") (name "unconnected-(M2-P0.18-Pad32)") (class "Default")
      (node (ref "M2") (pin "32") (pinfunction "P0.18_32") (pintype "bidirectional"))
    )
    (net (code "89") (name "unconnected-(M2-P0.19-Pad33)") (class "Default")
      (node (ref "M2") (pin "33") (pinfunction "P0.19_33") (pintype "bidirectional"))
    )
    (net (code "90") (name "unconnected-(M2-P0.20-Pad34)") (class "Default")
      (node (ref "M2") (pin "34") (pinfunction "P0.20_34") (pintype "bidirectional"))
    )
    (net (code "91") (name "unconnected-(M2-P0.22-Pad38)") (class "Default")
      (node (ref "M2") (pin "38") (pinfunction "P0.22_38") (pintype "bidirectional"))
    )
    (net (code "92") (name "unconnected-(M2-P0.23-Pad41)") (class "Default")
      (node (ref "M2") (pin "41") (pinfunction "P0.23_41") (pintype "bidirectional"))
    )
    (net (code "93") (name "unconnected-(M2-P0.24-Pad40)") (class "Default")
      (node (ref "M2") (pin "40") (pinfunction "P0.24_40") (pintype "bidirectional"))
    )
    (net (code "94") (name "unconnected-(M2-P0.25-Pad2)") (class "Default")
      (node (ref "M2") (pin "2") (pinfunction "P0.25_2") (pintype "bidirectional"))
    )
    (net (code "95") (name "unconnected-(M2-P0.26-Pad3)") (class "Default")
      (node (ref "M2") (pin "3") (pinfunction "P0.26_3") (pintype "bidirectional"))
    )
    (net (code "96") (name "unconnected-(M2-P0.27-Pad4)") (class "Default")
      (node (ref "M2") (pin "4") (pinfunction "P0.27_4") (pintype "bidirectional"))
    )
    (net (code "97") (name "unconnected-(M2-P0.28-Pad5)") (class "Default")
      (node (ref "M2") (pin "5") (pinfunction "P0.28_5") (pintype "bidirectional"))
    )
    (net (code "98") (name "unconnected-(M2-P0.29-Pad6)") (class "Default")
      (node (ref "M2") (pin "6") (pinfunction "P0.29_6") (pintype "bidirectional"))
    )
    (net (code "99") (name "unconnected-(M2-P0.30-Pad7)") (class "Default")
      (node (ref "M2") (pin "7") (pinfunction "P0.30_7") (pintype "bidirectional"))
    )
    (net (code "100") (name "unconnected-(M2-P0.31-Pad8)") (class "Default")
      (node (ref "M2") (pin "8") (pinfunction "P0.31_8") (pintype "bidirectional"))
    )
    (net (code "101") (name "unconnected-(S1-B0-Pad2)") (class "Default")
      (node (ref "S1") (pin "2") (pinfunction "B0_2") (pintype "bidirectional"))
    )
    (net (code "102") (name "unconnected-(S2-B0-Pad2)") (class "Default")
      (node (ref "S2") (pin "2") (pinfunction "B0_2") (pintype "bidirectional"))
    )
    (net (code "103") (name "unconnected-(S3-B0-Pad2)") (class "Default")
      (node (ref "S3") (pin "2") (pinfunction "B0_2") (pintype "bidirectional"))
    )
    (net (code "104") (name "unconnected-(S4-B0-Pad2)") (class "Default")
      (node (ref "S4") (pin "2") (pinfunction "B0_2") (pintype "bidirectional"))
    )
    (net (code "105") (name "unconnected-(S５-Pad1)") (class "Default")
      (node (ref "S５") (pin "1") (pinfunction "1_1") (pintype "bidirectional"))
    )
    (net (code "106") (name "unconnected-(S５-Pad3)") (class "Default")
      (node (ref "S５") (pin "3") (pinfunction "3_3") (pintype "bidirectional"))
    )
  )
)
